# Preamp_Schematic.net
KiCad netlist of a schematic drawn in EAGLE
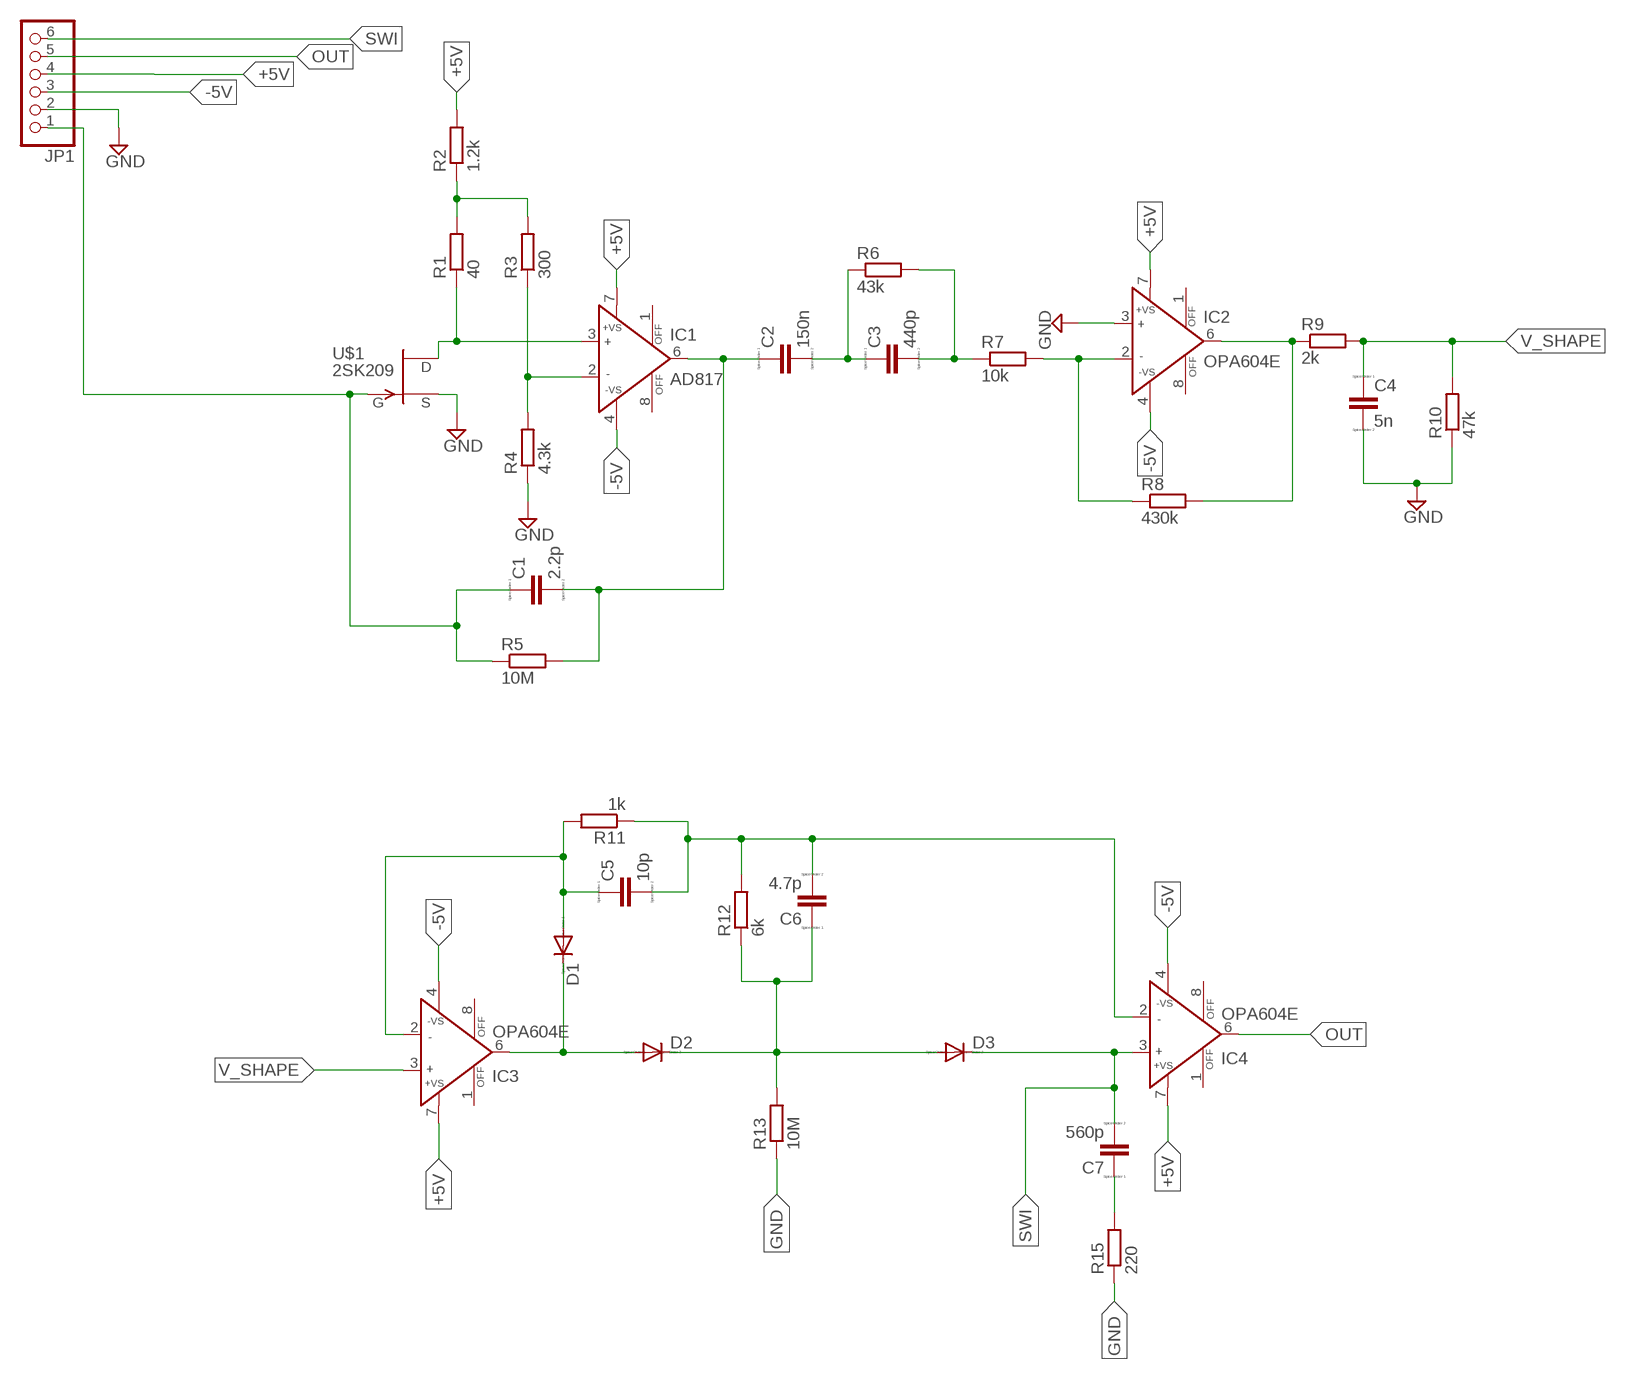
[diagram p0: schematic, sheet 1]

(export (version "E")
  (design (tool "Eeschema 10.0.6"))
  (components
    (comp (ref "C1")
      (value "2.2p")
      (footprint "eagle-import:C0805")
      (libsource (lib "eagle-import") (part "C"))
    )
    (comp (ref "C2")
      (value "150n")
      (footprint "eagle-import:C0805")
      (libsource (lib "eagle-import") (part "C"))
    )
    (comp (ref "C3")
      (value "440p")
      (footprint "eagle-import:C0805")
      (libsource (lib "eagle-import") (part "C"))
    )
    (comp (ref "C4")
      (value "5n")
      (footprint "eagle-import:C0805")
      (libsource (lib "eagle-import") (part "C"))
    )
    (comp (ref "C5")
      (value "10p")
      (footprint "eagle-import:C0805")
      (libsource (lib "eagle-import") (part "C"))
    )
    (comp (ref "C6")
      (value "4.7p")
      (footprint "eagle-import:C0805")
      (libsource (lib "eagle-import") (part "C"))
    )
    (comp (ref "C7")
      (value "560p")
      (footprint "eagle-import:C0805")
      (libsource (lib "eagle-import") (part "C"))
    )
    (comp (ref "D1")
      (value "DIODE-SOD123")
      (footprint "eagle-import:SOD123")
      (libsource (lib "eagle-import") (part "DIODE-SOD123"))
    )
    (comp (ref "D2")
      (value "DIODE-SOD123")
      (footprint "eagle-import:SOD123")
      (libsource (lib "eagle-import") (part "DIODE-SOD123"))
    )
    (comp (ref "D3")
      (value "DIODE-SOD123")
      (footprint "eagle-import:SOD123")
      (libsource (lib "eagle-import") (part "DIODE-SOD123"))
    )
    (comp (ref "IC1")
      (value "AD817")
      (footprint "eagle-import:SO8")
      (fields (field (name "MF") "ALTERA CORPORATION") (field (name "MPN") "AD817ARZ"))
      (libsource (lib "eagle-import") (part "AD817"))
    )
    (comp (ref "IC2")
      (value "OPA604E")
      (footprint "eagle-import:SO8")
      (fields (field (name "MF") "ALTERA CORPORATION") (field (name "MPN") "AD817ARZ"))
      (libsource (lib "eagle-import") (part "AD817"))
    )
    (comp (ref "IC3")
      (value "OPA604E")
      (footprint "eagle-import:SO8")
      (fields (field (name "MF") "ALTERA CORPORATION") (field (name "MPN") "AD817ARZ"))
      (libsource (lib "eagle-import") (part "AD817"))
    )
    (comp (ref "IC4")
      (value "OPA604E")
      (footprint "eagle-import:SO8")
      (fields (field (name "MF") "ALTERA CORPORATION") (field (name "MPN") "AD817ARZ"))
      (libsource (lib "eagle-import") (part "AD817"))
    )
    (comp (ref "JP1")
      (value "PINHD-1X6-3.5MM")
      (footprint "eagle-import:1X06-3.5MM")
      (libsource (lib "eagle-import") (part "PINHD-1X6-3.5MM"))
    )
    (comp (ref "R1")
      (value "40")
      (footprint "eagle-import:R0805")
      (libsource (lib "eagle-import") (part "R-EU_R0805"))
    )
    (comp (ref "R2")
      (value "1.2k")
      (footprint "eagle-import:R0805")
      (libsource (lib "eagle-import") (part "R-EU_R0805"))
    )
    (comp (ref "R3")
      (value "300")
      (footprint "eagle-import:R0805")
      (libsource (lib "eagle-import") (part "R-EU_R0805"))
    )
    (comp (ref "R4")
      (value "4.3k")
      (footprint "eagle-import:R0805")
      (libsource (lib "eagle-import") (part "R-EU_R0805"))
    )
    (comp (ref "R5")
      (value "10M")
      (footprint "eagle-import:R0805")
      (libsource (lib "eagle-import") (part "R-EU_R0805"))
    )
    (comp (ref "R6")
      (value "43k")
      (footprint "eagle-import:R0805")
      (libsource (lib "eagle-import") (part "R-EU_R0805"))
    )
    (comp (ref "R7")
      (value "10k")
      (footprint "eagle-import:R0805")
      (libsource (lib "eagle-import") (part "R-EU_R0805"))
    )
    (comp (ref "R8")
      (value "430k")
      (footprint "eagle-import:R0805")
      (libsource (lib "eagle-import") (part "R-EU_R0805"))
    )
    (comp (ref "R9")
      (value "2k")
      (footprint "eagle-import:R0805")
      (libsource (lib "eagle-import") (part "R-EU_R0805"))
    )
    (comp (ref "R10")
      (value "47k")
      (footprint "eagle-import:R0805")
      (libsource (lib "eagle-import") (part "R-EU_R0805"))
    )
    (comp (ref "R11")
      (value "1k")
      (footprint "eagle-import:R0805")
      (libsource (lib "eagle-import") (part "R-EU_R0805"))
    )
    (comp (ref "R12")
      (value "6k")
      (footprint "eagle-import:R0805")
      (libsource (lib "eagle-import") (part "R-EU_R0805"))
    )
    (comp (ref "R13")
      (value "10M")
      (footprint "eagle-import:R0805")
      (libsource (lib "eagle-import") (part "R-EU_R0805"))
    )
    (comp (ref "R15")
      (value "220")
      (footprint "eagle-import:R0805")
      (libsource (lib "eagle-import") (part "R-EU_R0805"))
    )
    (comp (ref "U$1")
      (value "2SK209")
      (footprint "eagle-import:2SK209")
      (libsource (lib "eagle-import") (part "2SK209"))
    )
  )
  (nets
    (net (code "1") (name "+5V") (class "Default")
      (node (ref "IC1") (pin "7") (pinfunction "+VS_7") (pintype "input"))
      (node (ref "IC2") (pin "7") (pinfunction "+VS_7") (pintype "input"))
      (node (ref "IC3") (pin "7") (pinfunction "+VS_7") (pintype "input"))
      (node (ref "IC4") (pin "7") (pinfunction "+VS_7") (pintype "input"))
      (node (ref "JP1") (pin "4") (pinfunction "4_4") (pintype "passive"))
      (node (ref "R2") (pin "2") (pinfunction "2_2") (pintype "passive"))
    )
    (net (code "2") (name "-5V") (class "Default")
      (node (ref "IC1") (pin "4") (pinfunction "-VS_4") (pintype "input"))
      (node (ref "IC2") (pin "4") (pinfunction "-VS_4") (pintype "input"))
      (node (ref "IC3") (pin "4") (pinfunction "-VS_4") (pintype "input"))
      (node (ref "IC4") (pin "4") (pinfunction "-VS_4") (pintype "input"))
      (node (ref "JP1") (pin "3") (pinfunction "3_3") (pintype "passive"))
    )
    (net (code "3") (name "GND") (class "Default")
      (node (ref "C4") (pin "2") (pinfunction "2_2") (pintype "passive"))
      (node (ref "IC2") (pin "3") (pinfunction "IN+_3") (pintype "input"))
      (node (ref "JP1") (pin "2") (pinfunction "2_2") (pintype "passive"))
      (node (ref "R10") (pin "1") (pinfunction "1_1") (pintype "passive"))
      (node (ref "R13") (pin "1") (pinfunction "1_1") (pintype "passive"))
      (node (ref "R15") (pin "1") (pinfunction "1_1") (pintype "passive"))
      (node (ref "R4") (pin "1") (pinfunction "1_1") (pintype "passive"))
      (node (ref "U$1") (pin "S") (pinfunction "S_S") (pintype "passive"))
    )
    (net (code "4") (name "Net-(C1-Pad1)") (class "Default")
      (node (ref "C1") (pin "1") (pinfunction "1_1") (pintype "passive"))
      (node (ref "JP1") (pin "1") (pinfunction "1_1") (pintype "passive"))
      (node (ref "R5") (pin "1") (pinfunction "1_1") (pintype "passive"))
      (node (ref "U$1") (pin "G") (pinfunction "G_G") (pintype "passive"))
    )
    (net (code "5") (name "Net-(C2-Pad2)") (class "Default")
      (node (ref "C2") (pin "2") (pinfunction "2_2") (pintype "passive"))
      (node (ref "C3") (pin "1") (pinfunction "1_1") (pintype "passive"))
      (node (ref "R6") (pin "1") (pinfunction "1_1") (pintype "passive"))
    )
    (net (code "6") (name "Net-(C3-Pad2)") (class "Default")
      (node (ref "C3") (pin "2") (pinfunction "2_2") (pintype "passive"))
      (node (ref "R6") (pin "2") (pinfunction "2_2") (pintype "passive"))
      (node (ref "R7") (pin "1") (pinfunction "1_1") (pintype "passive"))
    )
    (net (code "7") (name "Net-(C6-Pad1)") (class "Default")
      (node (ref "C6") (pin "1") (pinfunction "1_1") (pintype "passive"))
      (node (ref "D2") (pin "C") (pinfunction "C_C") (pintype "passive"))
      (node (ref "D3") (pin "A") (pinfunction "A_A") (pintype "passive"))
      (node (ref "R12") (pin "1") (pinfunction "1_1") (pintype "passive"))
      (node (ref "R13") (pin "2") (pinfunction "2_2") (pintype "passive"))
    )
    (net (code "8") (name "Net-(C7-Pad1)") (class "Default")
      (node (ref "C7") (pin "1") (pinfunction "1_1") (pintype "passive"))
      (node (ref "R15") (pin "2") (pinfunction "2_2") (pintype "passive"))
    )
    (net (code "9") (name "Net-(IC1-IN+)") (class "Default")
      (node (ref "IC1") (pin "3") (pinfunction "IN+_3") (pintype "input"))
      (node (ref "R1") (pin "1") (pinfunction "1_1") (pintype "passive"))
      (node (ref "U$1") (pin "D") (pinfunction "D_D") (pintype "passive"))
    )
    (net (code "10") (name "Net-(IC1-IN-)") (class "Default")
      (node (ref "IC1") (pin "2") (pinfunction "IN-_2") (pintype "input"))
      (node (ref "R3") (pin "1") (pinfunction "1_1") (pintype "passive"))
      (node (ref "R4") (pin "2") (pinfunction "2_2") (pintype "passive"))
    )
    (net (code "11") (name "Net-(IC1-OUT)") (class "Default")
      (node (ref "C1") (pin "2") (pinfunction "2_2") (pintype "passive"))
      (node (ref "C2") (pin "1") (pinfunction "1_1") (pintype "passive"))
      (node (ref "IC1") (pin "6") (pinfunction "OUT_6") (pintype "output"))
      (node (ref "R5") (pin "2") (pinfunction "2_2") (pintype "passive"))
    )
    (net (code "12") (name "Net-(IC2-IN-)") (class "Default")
      (node (ref "IC2") (pin "2") (pinfunction "IN-_2") (pintype "input"))
      (node (ref "R7") (pin "2") (pinfunction "2_2") (pintype "passive"))
      (node (ref "R8") (pin "1") (pinfunction "1_1") (pintype "passive"))
    )
    (net (code "13") (name "Net-(IC2-OUT)") (class "Default")
      (node (ref "IC2") (pin "6") (pinfunction "OUT_6") (pintype "output"))
      (node (ref "R8") (pin "2") (pinfunction "2_2") (pintype "passive"))
      (node (ref "R9") (pin "1") (pinfunction "1_1") (pintype "passive"))
    )
    (net (code "14") (name "Net-(IC3-IN-)") (class "Default")
      (node (ref "C5") (pin "1") (pinfunction "1_1") (pintype "passive"))
      (node (ref "D1") (pin "A") (pinfunction "A_A") (pintype "passive"))
      (node (ref "IC3") (pin "2") (pinfunction "IN-_2") (pintype "input"))
      (node (ref "R11") (pin "2") (pinfunction "2_2") (pintype "passive"))
    )
    (net (code "15") (name "Net-(IC3-OUT)") (class "Default")
      (node (ref "D1") (pin "C") (pinfunction "C_C") (pintype "passive"))
      (node (ref "D2") (pin "A") (pinfunction "A_A") (pintype "passive"))
      (node (ref "IC3") (pin "6") (pinfunction "OUT_6") (pintype "output"))
    )
    (net (code "16") (name "Net-(IC4-IN-)") (class "Default")
      (node (ref "C5") (pin "2") (pinfunction "2_2") (pintype "passive"))
      (node (ref "C6") (pin "2") (pinfunction "2_2") (pintype "passive"))
      (node (ref "IC4") (pin "2") (pinfunction "IN-_2") (pintype "input"))
      (node (ref "R11") (pin "1") (pinfunction "1_1") (pintype "passive"))
      (node (ref "R12") (pin "2") (pinfunction "2_2") (pintype "passive"))
    )
    (net (code "17") (name "Net-(R1-Pad2)") (class "Default")
      (node (ref "R1") (pin "2") (pinfunction "2_2") (pintype "passive"))
      (node (ref "R2") (pin "1") (pinfunction "1_1") (pintype "passive"))
      (node (ref "R3") (pin "2") (pinfunction "2_2") (pintype "passive"))
    )
    (net (code "18") (name "OUT") (class "Default")
      (node (ref "IC4") (pin "6") (pinfunction "OUT_6") (pintype "output"))
      (node (ref "JP1") (pin "5") (pinfunction "5_5") (pintype "passive"))
    )
    (net (code "19") (name "SWI") (class "Default")
      (node (ref "C7") (pin "2") (pinfunction "2_2") (pintype "passive"))
      (node (ref "D3") (pin "C") (pinfunction "C_C") (pintype "passive"))
      (node (ref "IC4") (pin "3") (pinfunction "IN+_3") (pintype "input"))
      (node (ref "JP1") (pin "6") (pinfunction "6_6") (pintype "passive"))
    )
    (net (code "20") (name "V_SHAPE") (class "Default")
      (node (ref "C4") (pin "1") (pinfunction "1_1") (pintype "passive"))
      (node (ref "IC3") (pin "3") (pinfunction "IN+_3") (pintype "input"))
      (node (ref "R10") (pin "2") (pinfunction "2_2") (pintype "passive"))
      (node (ref "R9") (pin "2") (pinfunction "2_2") (pintype "passive"))
    )
    (net (code "21") (name "unconnected-(IC1-OFF-Pad1)") (class "Default")
      (node (ref "IC1") (pin "1") (pinfunction "OFF_1") (pintype "passive"))
    )
    (net (code "22") (name "unconnected-(IC1-OFF-Pad8)") (class "Default")
      (node (ref "IC1") (pin "8") (pinfunction "OFF_8") (pintype "passive"))
    )
    (net (code "23") (name "unconnected-(IC2-OFF-Pad1)") (class "Default")
      (node (ref "IC2") (pin "1") (pinfunction "OFF_1") (pintype "passive"))
    )
    (net (code "24") (name "unconnected-(IC2-OFF-Pad8)") (class "Default")
      (node (ref "IC2") (pin "8") (pinfunction "OFF_8") (pintype "passive"))
    )
    (net (code "25") (name "unconnected-(IC3-OFF-Pad1)") (class "Default")
      (node (ref "IC3") (pin "1") (pinfunction "OFF_1") (pintype "passive"))
    )
    (net (code "26") (name "unconnected-(IC3-OFF-Pad8)") (class "Default")
      (node (ref "IC3") (pin "8") (pinfunction "OFF_8") (pintype "passive"))
    )
    (net (code "27") (name "unconnected-(IC4-OFF-Pad1)") (class "Default")
      (node (ref "IC4") (pin "1") (pinfunction "OFF_1") (pintype "passive"))
    )
    (net (code "28") (name "unconnected-(IC4-OFF-Pad8)") (class "Default")
      (node (ref "IC4") (pin "8") (pinfunction "OFF_8") (pintype "passive"))
    )
  )
)
